# Sheet2.net
KiCad netlist of a schematic drawn in Altium Designer
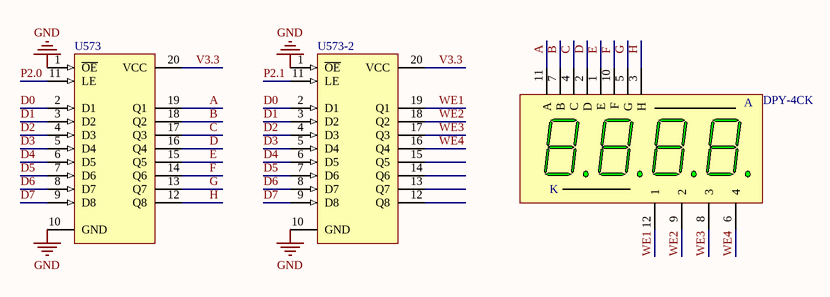
[diagram p0: Sheet2.SchDoc]

(export (version "E")
  (design (tool "Eeschema 10.0.6"))
  (components
    (comp (ref "DPY-4CK")
      (value "DPY-4CK")
      (footprint "DYP-4BIT")
      (description "共阴4位数码管")
      (libsource (lib "fszhang") (part "DPY-4CK"))
    )
    (comp (ref "U573")
      (value "SN74HC573N")
      (footprint "N020D")
      (description "Octal D-Type Transparent Latch with 3-State Outputs")
      (fields (field (name "PUBLISHER") "Altium Limited"))
      (libsource (lib "TI Logic Latch") (part "SN74HC573N"))
    )
    (comp (ref "U573-2")
      (value "SN74HC573N")
      (footprint "N020D")
      (description "Octal D-Type Transparent Latch with 3-State Outputs")
      (fields (field (name "PUBLISHER") "Altium Limited"))
      (libsource (lib "TI Logic Latch") (part "SN74HC573N"))
    )
  )
  (nets
    (net (code "1") (name "/A") (class "Default")
      (node (ref "DPY-4CK") (pin "11") (pinfunction "A_11") (pintype "passive"))
      (node (ref "U573") (pin "19") (pinfunction "Q1_19") (pintype "tri_state"))
    )
    (net (code "2") (name "/B") (class "Default")
      (node (ref "DPY-4CK") (pin "7") (pinfunction "B_7") (pintype "passive"))
      (node (ref "U573") (pin "18") (pinfunction "Q2_18") (pintype "tri_state"))
    )
    (net (code "3") (name "/C") (class "Default")
      (node (ref "DPY-4CK") (pin "4") (pinfunction "C_4") (pintype "passive"))
      (node (ref "U573") (pin "17") (pinfunction "Q3_17") (pintype "tri_state"))
    )
    (net (code "4") (name "/D") (class "Default")
      (node (ref "DPY-4CK") (pin "2") (pinfunction "D_2") (pintype "passive"))
      (node (ref "U573") (pin "16") (pinfunction "Q4_16") (pintype "tri_state"))
    )
    (net (code "5") (name "/D0") (class "Default")
      (node (ref "U573") (pin "2") (pinfunction "D1_2") (pintype "input"))
      (node (ref "U573-2") (pin "2") (pinfunction "D1_2") (pintype "input"))
    )
    (net (code "6") (name "/D1") (class "Default")
      (node (ref "U573") (pin "3") (pinfunction "D2_3") (pintype "input"))
      (node (ref "U573-2") (pin "3") (pinfunction "D2_3") (pintype "input"))
    )
    (net (code "7") (name "/D2") (class "Default")
      (node (ref "U573") (pin "4") (pinfunction "D3_4") (pintype "input"))
      (node (ref "U573-2") (pin "4") (pinfunction "D3_4") (pintype "input"))
    )
    (net (code "8") (name "/D3") (class "Default")
      (node (ref "U573") (pin "5") (pinfunction "D4_5") (pintype "input"))
      (node (ref "U573-2") (pin "5") (pinfunction "D4_5") (pintype "input"))
    )
    (net (code "9") (name "/D4") (class "Default")
      (node (ref "U573") (pin "6") (pinfunction "D5_6") (pintype "input"))
      (node (ref "U573-2") (pin "6") (pinfunction "D5_6") (pintype "input"))
    )
    (net (code "10") (name "/D5") (class "Default")
      (node (ref "U573") (pin "7") (pinfunction "D6_7") (pintype "input"))
      (node (ref "U573-2") (pin "7") (pinfunction "D6_7") (pintype "input"))
    )
    (net (code "11") (name "/D6") (class "Default")
      (node (ref "U573") (pin "8") (pinfunction "D7_8") (pintype "input"))
      (node (ref "U573-2") (pin "8") (pinfunction "D7_8") (pintype "input"))
    )
    (net (code "12") (name "/D7") (class "Default")
      (node (ref "U573") (pin "9") (pinfunction "D8_9") (pintype "input"))
      (node (ref "U573-2") (pin "9") (pinfunction "D8_9") (pintype "input"))
    )
    (net (code "13") (name "/E") (class "Default")
      (node (ref "DPY-4CK") (pin "1") (pinfunction "E_1") (pintype "passive"))
      (node (ref "U573") (pin "15") (pinfunction "Q5_15") (pintype "tri_state"))
    )
    (net (code "14") (name "/F") (class "Default")
      (node (ref "DPY-4CK") (pin "10") (pinfunction "F_10") (pintype "passive"))
      (node (ref "U573") (pin "14") (pinfunction "Q6_14") (pintype "tri_state"))
    )
    (net (code "15") (name "/G") (class "Default")
      (node (ref "DPY-4CK") (pin "5") (pinfunction "G_5") (pintype "passive"))
      (node (ref "U573") (pin "13") (pinfunction "Q7_13") (pintype "tri_state"))
    )
    (net (code "16") (name "/H") (class "Default")
      (node (ref "DPY-4CK") (pin "3") (pinfunction "H_3") (pintype "passive"))
      (node (ref "U573") (pin "12") (pinfunction "Q8_12") (pintype "tri_state"))
    )
    (net (code "17") (name "/P2.0") (class "Default")
      (node (ref "U573") (pin "11") (pinfunction "LE_11") (pintype "input"))
    )
    (net (code "18") (name "/P2.1") (class "Default")
      (node (ref "U573-2") (pin "11") (pinfunction "LE_11") (pintype "input"))
    )
    (net (code "19") (name "/V3.3") (class "Default")
      (node (ref "U573") (pin "20") (pinfunction "VCC_20") (pintype "power_in"))
      (node (ref "U573-2") (pin "20") (pinfunction "VCC_20") (pintype "power_in"))
    )
    (net (code "20") (name "/WE1") (class "Default")
      (node (ref "DPY-4CK") (pin "12") (pinfunction "1_12") (pintype "passive"))
      (node (ref "U573-2") (pin "19") (pinfunction "Q1_19") (pintype "tri_state"))
    )
    (net (code "21") (name "/WE2") (class "Default")
      (node (ref "DPY-4CK") (pin "9") (pinfunction "2_9") (pintype "passive"))
      (node (ref "U573-2") (pin "18") (pinfunction "Q2_18") (pintype "tri_state"))
    )
    (net (code "22") (name "/WE3") (class "Default")
      (node (ref "DPY-4CK") (pin "8") (pinfunction "3_8") (pintype "passive"))
      (node (ref "U573-2") (pin "17") (pinfunction "Q3_17") (pintype "tri_state"))
    )
    (net (code "23") (name "/WE4") (class "Default")
      (node (ref "DPY-4CK") (pin "6") (pinfunction "4_6") (pintype "passive"))
      (node (ref "U573-2") (pin "16") (pinfunction "Q4_16") (pintype "tri_state"))
    )
    (net (code "24") (name "GND") (class "Default")
      (node (ref "U573") (pin "1") (pinfunction "~{OE}_1") (pintype "input"))
      (node (ref "U573") (pin "10") (pinfunction "GND_10") (pintype "power_in"))
      (node (ref "U573-2") (pin "1") (pinfunction "~{OE}_1") (pintype "input"))
      (node (ref "U573-2") (pin "10") (pinfunction "GND_10") (pintype "power_in"))
    )
    (net (code "25") (name "unconnected-(U573-2-Q5-Pad15)") (class "Default")
      (node (ref "U573-2") (pin "15") (pinfunction "Q5_15") (pintype "tri_state"))
    )
    (net (code "26") (name "unconnected-(U573-2-Q6-Pad14)") (class "Default")
      (node (ref "U573-2") (pin "14") (pinfunction "Q6_14") (pintype "tri_state"))
    )
    (net (code "27") (name "unconnected-(U573-2-Q7-Pad13)") (class "Default")
      (node (ref "U573-2") (pin "13") (pinfunction "Q7_13") (pintype "tri_state"))
    )
    (net (code "28") (name "unconnected-(U573-2-Q8-Pad12)") (class "Default")
      (node (ref "U573-2") (pin "12") (pinfunction "Q8_12") (pintype "tri_state"))
    )
  )
)
